# GateWayMainBoard.net
KiCad netlist of a schematic drawn in Altium Designer
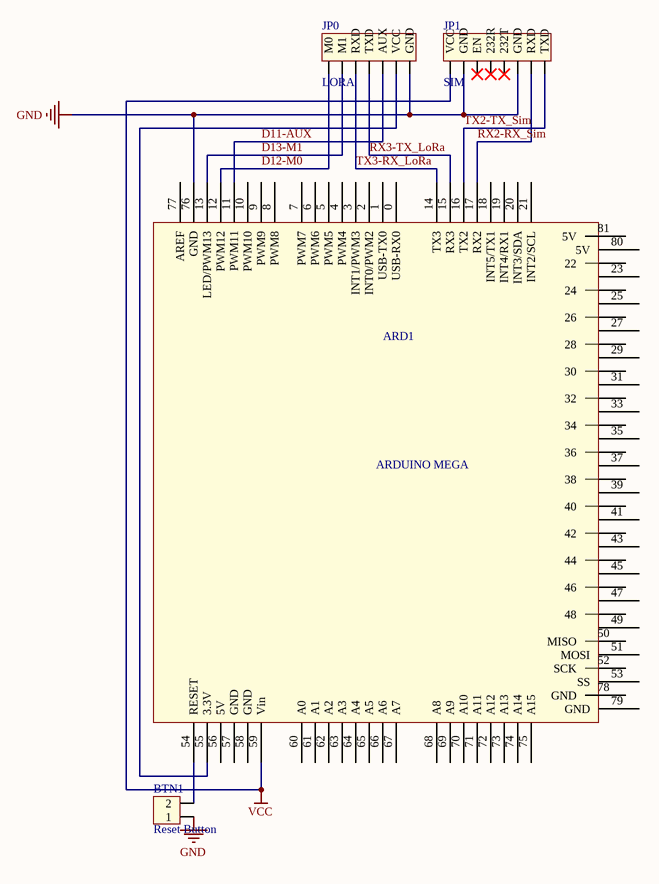
[diagram p0: GateWayMainBoard.SchDoc]

(export (version "E")
  (design (tool "Eeschema 10.0.6"))
  (components
    (comp (ref "ARD1")
      (value "ARDUINO MEGA")
      (footprint "Arduino:Arduino")
      (libsource (lib "*") (part "Arduino"))
    )
    (comp (ref "BTN1")
      (value "Reset Button")
      (footprint "HED2")
      (description "Header 2 (Green)")
      (libsource (lib "syhaunguyen") (part "Hed2"))
    )
    (comp (ref "JP0")
      (value "LORA")
      (footprint "syhaunguyen:CON7")
      (description "Connector 7")
      (libsource (lib "syhaunguyen") (part "Con7"))
    )
    (comp (ref "JP1")
      (value "SIM")
      (footprint "syhaunguyen:CON8")
      (description "Connector 8")
      (libsource (lib "*") (part "Con8"))
    )
  )
  (nets
    (net (code "1") (name "/D11-AUX") (class "Default")
      (node (ref "ARD1") (pin "11") (pinfunction "PWM11_11") (pintype "passive"))
      (node (ref "JP0") (pin "5") (pinfunction "AUX_5") (pintype "passive"))
    )
    (net (code "2") (name "/D12-M0") (class "Default")
      (node (ref "ARD1") (pin "12") (pinfunction "PWM12_12") (pintype "passive"))
      (node (ref "JP0") (pin "1") (pinfunction "M0_1") (pintype "passive"))
    )
    (net (code "3") (name "/D13-M1") (class "Default")
      (node (ref "ARD1") (pin "13") (pinfunction "LED/PWM13_13") (pintype "passive"))
      (node (ref "JP0") (pin "2") (pinfunction "M1_2") (pintype "passive"))
    )
    (net (code "4") (name "/RX2-RX_Sim") (class "Default")
      (node (ref "ARD1") (pin "17") (pinfunction "RX2_17") (pintype "passive"))
      (node (ref "JP1") (pin "7") (pinfunction "RXD_7") (pintype "passive"))
    )
    (net (code "5") (name "/RX3-TX_LoRa") (class "Default")
      (node (ref "ARD1") (pin "15") (pinfunction "RX3_15") (pintype "passive"))
      (node (ref "JP0") (pin "4") (pinfunction "TXD_4") (pintype "passive"))
    )
    (net (code "6") (name "/TX2-TX_Sim") (class "Default")
      (node (ref "ARD1") (pin "16") (pinfunction "TX2_16") (pintype "passive"))
      (node (ref "JP1") (pin "8") (pinfunction "TXD_8") (pintype "passive"))
    )
    (net (code "7") (name "/TX3-RX_LoRa") (class "Default")
      (node (ref "ARD1") (pin "14") (pinfunction "TX3_14") (pintype "passive"))
      (node (ref "JP0") (pin "3") (pinfunction "RXD_3") (pintype "passive"))
    )
    (net (code "8") (name "GND") (class "Default")
      (node (ref "ARD1") (pin "76") (pinfunction "GND_76") (pintype "passive"))
      (node (ref "BTN1") (pin "1") (pinfunction "1_1") (pintype "passive"))
      (node (ref "JP0") (pin "7") (pinfunction "GND_7") (pintype "passive"))
      (node (ref "JP1") (pin "2") (pinfunction "GND_2") (pintype "passive"))
      (node (ref "JP1") (pin "6") (pinfunction "GND_6") (pintype "passive"))
    )
    (net (code "9") (name "Net-(ARD1-3.3V)") (class "Default")
      (node (ref "ARD1") (pin "55") (pinfunction "3.3V_55") (pintype "passive"))
      (node (ref "JP0") (pin "6") (pinfunction "VCC_6") (pintype "passive"))
    )
    (net (code "10") (name "Net-(ARD1-RESET)") (class "Default")
      (node (ref "ARD1") (pin "54") (pinfunction "RESET_54") (pintype "passive"))
      (node (ref "BTN1") (pin "2") (pinfunction "2_2") (pintype "passive"))
    )
    (net (code "11") (name "VCC") (class "Default")
      (node (ref "ARD1") (pin "59") (pinfunction "Vin_59") (pintype "passive"))
      (node (ref "JP1") (pin "1") (pinfunction "VCC_1") (pintype "passive"))
    )
    (net (code "12") (name "unconnected-(ARD1-5V-Pad56)") (class "Default")
      (node (ref "ARD1") (pin "56") (pinfunction "5V_56") (pintype "passive"))
    )
    (net (code "13") (name "unconnected-(ARD1-5V-Pad80)") (class "Default")
      (node (ref "ARD1") (pin "80") (pinfunction "5V_80") (pintype "passive"))
    )
    (net (code "14") (name "unconnected-(ARD1-5V-Pad81)") (class "Default")
      (node (ref "ARD1") (pin "81") (pinfunction "5V_81") (pintype "passive"))
    )
    (net (code "15") (name "unconnected-(ARD1-A0-Pad60)") (class "Default")
      (node (ref "ARD1") (pin "60") (pinfunction "A0_60") (pintype "passive"))
    )
    (net (code "16") (name "unconnected-(ARD1-A1-Pad61)") (class "Default")
      (node (ref "ARD1") (pin "61") (pinfunction "A1_61") (pintype "passive"))
    )
    (net (code "17") (name "unconnected-(ARD1-A2-Pad62)") (class "Default")
      (node (ref "ARD1") (pin "62") (pinfunction "A2_62") (pintype "passive"))
    )
    (net (code "18") (name "unconnected-(ARD1-A3-Pad63)") (class "Default")
      (node (ref "ARD1") (pin "63") (pinfunction "A3_63") (pintype "passive"))
    )
    (net (code "19") (name "unconnected-(ARD1-A4-Pad64)") (class "Default")
      (node (ref "ARD1") (pin "64") (pinfunction "A4_64") (pintype "passive"))
    )
    (net (code "20") (name "unconnected-(ARD1-A5-Pad65)") (class "Default")
      (node (ref "ARD1") (pin "65") (pinfunction "A5_65") (pintype "passive"))
    )
    (net (code "21") (name "unconnected-(ARD1-A6-Pad66)") (class "Default")
      (node (ref "ARD1") (pin "66") (pinfunction "A6_66") (pintype "passive"))
    )
    (net (code "22") (name "unconnected-(ARD1-A7-Pad67)") (class "Default")
      (node (ref "ARD1") (pin "67") (pinfunction "A7_67") (pintype "passive"))
    )
    (net (code "23") (name "unconnected-(ARD1-A8-Pad68)") (class "Default")
      (node (ref "ARD1") (pin "68") (pinfunction "A8_68") (pintype "passive"))
    )
    (net (code "24") (name "unconnected-(ARD1-A9-Pad69)") (class "Default")
      (node (ref "ARD1") (pin "69") (pinfunction "A9_69") (pintype "passive"))
    )
    (net (code "25") (name "unconnected-(ARD1-A10-Pad70)") (class "Default")
      (node (ref "ARD1") (pin "70") (pinfunction "A10_70") (pintype "passive"))
    )
    (net (code "26") (name "unconnected-(ARD1-A11-Pad71)") (class "Default")
      (node (ref "ARD1") (pin "71") (pinfunction "A11_71") (pintype "passive"))
    )
    (net (code "27") (name "unconnected-(ARD1-A12-Pad72)") (class "Default")
      (node (ref "ARD1") (pin "72") (pinfunction "A12_72") (pintype "passive"))
    )
    (net (code "28") (name "unconnected-(ARD1-A13-Pad73)") (class "Default")
      (node (ref "ARD1") (pin "73") (pinfunction "A13_73") (pintype "passive"))
    )
    (net (code "29") (name "unconnected-(ARD1-A14-Pad74)") (class "Default")
      (node (ref "ARD1") (pin "74") (pinfunction "A14_74") (pintype "passive"))
    )
    (net (code "30") (name "unconnected-(ARD1-A15-Pad75)") (class "Default")
      (node (ref "ARD1") (pin "75") (pinfunction "A15_75") (pintype "passive"))
    )
    (net (code "31") (name "unconnected-(ARD1-AREF-Pad77)") (class "Default")
      (node (ref "ARD1") (pin "77") (pinfunction "AREF_77") (pintype "passive"))
    )
    (net (code "32") (name "unconnected-(ARD1-GND-Pad57)") (class "Default")
      (node (ref "ARD1") (pin "57") (pinfunction "GND_57") (pintype "passive"))
    )
    (net (code "33") (name "unconnected-(ARD1-GND-Pad58)") (class "Default")
      (node (ref "ARD1") (pin "58") (pinfunction "GND_58") (pintype "passive"))
    )
    (net (code "34") (name "unconnected-(ARD1-GND-Pad78)") (class "Default")
      (node (ref "ARD1") (pin "78") (pinfunction "GND_78") (pintype "passive"))
    )
    (net (code "35") (name "unconnected-(ARD1-GND-Pad79)") (class "Default")
      (node (ref "ARD1") (pin "79") (pinfunction "GND_79") (pintype "passive"))
    )
    (net (code "36") (name "unconnected-(ARD1-INT0{slash}PWM2-Pad2)") (class "Default")
      (node (ref "ARD1") (pin "2") (pinfunction "INT0/PWM2_2") (pintype "passive"))
    )
    (net (code "37") (name "unconnected-(ARD1-INT1{slash}PWM3-Pad3)") (class "Default")
      (node (ref "ARD1") (pin "3") (pinfunction "INT1/PWM3_3") (pintype "passive"))
    )
    (net (code "38") (name "unconnected-(ARD1-INT2{slash}SCL-Pad21)") (class "Default")
      (node (ref "ARD1") (pin "21") (pinfunction "INT2/SCL_21") (pintype "passive"))
    )
    (net (code "39") (name "unconnected-(ARD1-INT3{slash}SDA-Pad20)") (class "Default")
      (node (ref "ARD1") (pin "20") (pinfunction "INT3/SDA_20") (pintype "passive"))
    )
    (net (code "40") (name "unconnected-(ARD1-INT4{slash}RX1-Pad19)") (class "Default")
      (node (ref "ARD1") (pin "19") (pinfunction "INT4/RX1_19") (pintype "passive"))
    )
    (net (code "41") (name "unconnected-(ARD1-INT5{slash}TX1-Pad18)") (class "Default")
      (node (ref "ARD1") (pin "18") (pinfunction "INT5/TX1_18") (pintype "passive"))
    )
    (net (code "42") (name "unconnected-(ARD1-MISO-Pad50)") (class "Default")
      (node (ref "ARD1") (pin "50") (pinfunction "MISO_50") (pintype "passive"))
    )
    (net (code "43") (name "unconnected-(ARD1-MOSI-Pad51)") (class "Default")
      (node (ref "ARD1") (pin "51") (pinfunction "MOSI_51") (pintype "passive"))
    )
    (net (code "44") (name "unconnected-(ARD1-PWM4-Pad4)") (class "Default")
      (node (ref "ARD1") (pin "4") (pinfunction "PWM4_4") (pintype "passive"))
    )
    (net (code "45") (name "unconnected-(ARD1-PWM5-Pad5)") (class "Default")
      (node (ref "ARD1") (pin "5") (pinfunction "PWM5_5") (pintype "passive"))
    )
    (net (code "46") (name "unconnected-(ARD1-PWM6-Pad6)") (class "Default")
      (node (ref "ARD1") (pin "6") (pinfunction "PWM6_6") (pintype "passive"))
    )
    (net (code "47") (name "unconnected-(ARD1-PWM7-Pad7)") (class "Default")
      (node (ref "ARD1") (pin "7") (pinfunction "PWM7_7") (pintype "passive"))
    )
    (net (code "48") (name "unconnected-(ARD1-PWM8-Pad8)") (class "Default")
      (node (ref "ARD1") (pin "8") (pinfunction "PWM8_8") (pintype "passive"))
    )
    (net (code "49") (name "unconnected-(ARD1-PWM9-Pad9)") (class "Default")
      (node (ref "ARD1") (pin "9") (pinfunction "PWM9_9") (pintype "passive"))
    )
    (net (code "50") (name "unconnected-(ARD1-PWM10-Pad10)") (class "Default")
      (node (ref "ARD1") (pin "10") (pinfunction "PWM10_10") (pintype "passive"))
    )
    (net (code "51") (name "unconnected-(ARD1-Pad22)") (class "Default")
      (node (ref "ARD1") (pin "22") (pinfunction "22_22") (pintype "passive"))
    )
    (net (code "52") (name "unconnected-(ARD1-Pad23)") (class "Default")
      (node (ref "ARD1") (pin "23") (pinfunction "23_23") (pintype "passive"))
    )
    (net (code "53") (name "unconnected-(ARD1-Pad24)") (class "Default")
      (node (ref "ARD1") (pin "24") (pinfunction "24_24") (pintype "passive"))
    )
    (net (code "54") (name "unconnected-(ARD1-Pad25)") (class "Default")
      (node (ref "ARD1") (pin "25") (pinfunction "25_25") (pintype "passive"))
    )
    (net (code "55") (name "unconnected-(ARD1-Pad26)") (class "Default")
      (node (ref "ARD1") (pin "26") (pinfunction "26_26") (pintype "passive"))
    )
    (net (code "56") (name "unconnected-(ARD1-Pad27)") (class "Default")
      (node (ref "ARD1") (pin "27") (pinfunction "27_27") (pintype "passive"))
    )
    (net (code "57") (name "unconnected-(ARD1-Pad28)") (class "Default")
      (node (ref "ARD1") (pin "28") (pinfunction "28_28") (pintype "passive"))
    )
    (net (code "58") (name "unconnected-(ARD1-Pad29)") (class "Default")
      (node (ref "ARD1") (pin "29") (pinfunction "29_29") (pintype "passive"))
    )
    (net (code "59") (name "unconnected-(ARD1-Pad30)") (class "Default")
      (node (ref "ARD1") (pin "30") (pinfunction "30_30") (pintype "passive"))
    )
    (net (code "60") (name "unconnected-(ARD1-Pad31)") (class "Default")
      (node (ref "ARD1") (pin "31") (pinfunction "31_31") (pintype "passive"))
    )
    (net (code "61") (name "unconnected-(ARD1-Pad32)") (class "Default")
      (node (ref "ARD1") (pin "32") (pinfunction "32_32") (pintype "passive"))
    )
    (net (code "62") (name "unconnected-(ARD1-Pad33)") (class "Default")
      (node (ref "ARD1") (pin "33") (pinfunction "33_33") (pintype "passive"))
    )
    (net (code "63") (name "unconnected-(ARD1-Pad34)") (class "Default")
      (node (ref "ARD1") (pin "34") (pinfunction "34_34") (pintype "passive"))
    )
    (net (code "64") (name "unconnected-(ARD1-Pad35)") (class "Default")
      (node (ref "ARD1") (pin "35") (pinfunction "35_35") (pintype "passive"))
    )
    (net (code "65") (name "unconnected-(ARD1-Pad36)") (class "Default")
      (node (ref "ARD1") (pin "36") (pinfunction "36_36") (pintype "passive"))
    )
    (net (code "66") (name "unconnected-(ARD1-Pad37)") (class "Default")
      (node (ref "ARD1") (pin "37") (pinfunction "37_37") (pintype "passive"))
    )
    (net (code "67") (name "unconnected-(ARD1-Pad38)") (class "Default")
      (node (ref "ARD1") (pin "38") (pinfunction "38_38") (pintype "passive"))
    )
    (net (code "68") (name "unconnected-(ARD1-Pad39)") (class "Default")
      (node (ref "ARD1") (pin "39") (pinfunction "39_39") (pintype "passive"))
    )
    (net (code "69") (name "unconnected-(ARD1-Pad40)") (class "Default")
      (node (ref "ARD1") (pin "40") (pinfunction "40_40") (pintype "passive"))
    )
    (net (code "70") (name "unconnected-(ARD1-Pad41)") (class "Default")
      (node (ref "ARD1") (pin "41") (pinfunction "41_41") (pintype "passive"))
    )
    (net (code "71") (name "unconnected-(ARD1-Pad42)") (class "Default")
      (node (ref "ARD1") (pin "42") (pinfunction "42_42") (pintype "passive"))
    )
    (net (code "72") (name "unconnected-(ARD1-Pad43)") (class "Default")
      (node (ref "ARD1") (pin "43") (pinfunction "43_43") (pintype "passive"))
    )
    (net (code "73") (name "unconnected-(ARD1-Pad44)") (class "Default")
      (node (ref "ARD1") (pin "44") (pinfunction "44_44") (pintype "passive"))
    )
    (net (code "74") (name "unconnected-(ARD1-Pad45)") (class "Default")
      (node (ref "ARD1") (pin "45") (pinfunction "45_45") (pintype "passive"))
    )
    (net (code "75") (name "unconnected-(ARD1-Pad46)") (class "Default")
      (node (ref "ARD1") (pin "46") (pinfunction "46_46") (pintype "passive"))
    )
    (net (code "76") (name "unconnected-(ARD1-Pad47)") (class "Default")
      (node (ref "ARD1") (pin "47") (pinfunction "47_47") (pintype "passive"))
    )
    (net (code "77") (name "unconnected-(ARD1-Pad48)") (class "Default")
      (node (ref "ARD1") (pin "48") (pinfunction "48_48") (pintype "passive"))
    )
    (net (code "78") (name "unconnected-(ARD1-Pad49)") (class "Default")
      (node (ref "ARD1") (pin "49") (pinfunction "49_49") (pintype "passive"))
    )
    (net (code "79") (name "unconnected-(ARD1-SCK-Pad52)") (class "Default")
      (node (ref "ARD1") (pin "52") (pinfunction "SCK_52") (pintype "passive"))
    )
    (net (code "80") (name "unconnected-(ARD1-SS-Pad53)") (class "Default")
      (node (ref "ARD1") (pin "53") (pinfunction "SS_53") (pintype "passive"))
    )
    (net (code "81") (name "unconnected-(ARD1-USB-RX0-Pad0)") (class "Default")
      (node (ref "ARD1") (pin "0") (pinfunction "USB-RX0_0") (pintype "passive"))
    )
    (net (code "82") (name "unconnected-(ARD1-USB-TX0-Pad1)") (class "Default")
      (node (ref "ARD1") (pin "1") (pinfunction "USB-TX0_1") (pintype "passive"))
    )
    (net (code "83") (name "unconnected-(JP1-232R-Pad4)") (class "Default")
      (node (ref "JP1") (pin "4") (pinfunction "232R_4") (pintype "passive+no_connect"))
    )
    (net (code "84") (name "unconnected-(JP1-232T-Pad5)") (class "Default")
      (node (ref "JP1") (pin "5") (pinfunction "232T_5") (pintype "passive+no_connect"))
    )
    (net (code "85") (name "unconnected-(JP1-EN-Pad3)") (class "Default")
      (node (ref "JP1") (pin "3") (pinfunction "EN_3") (pintype "passive+no_connect"))
    )
  )
)
